# powerboard.net
KiCad netlist of a schematic drawn in EAGLE
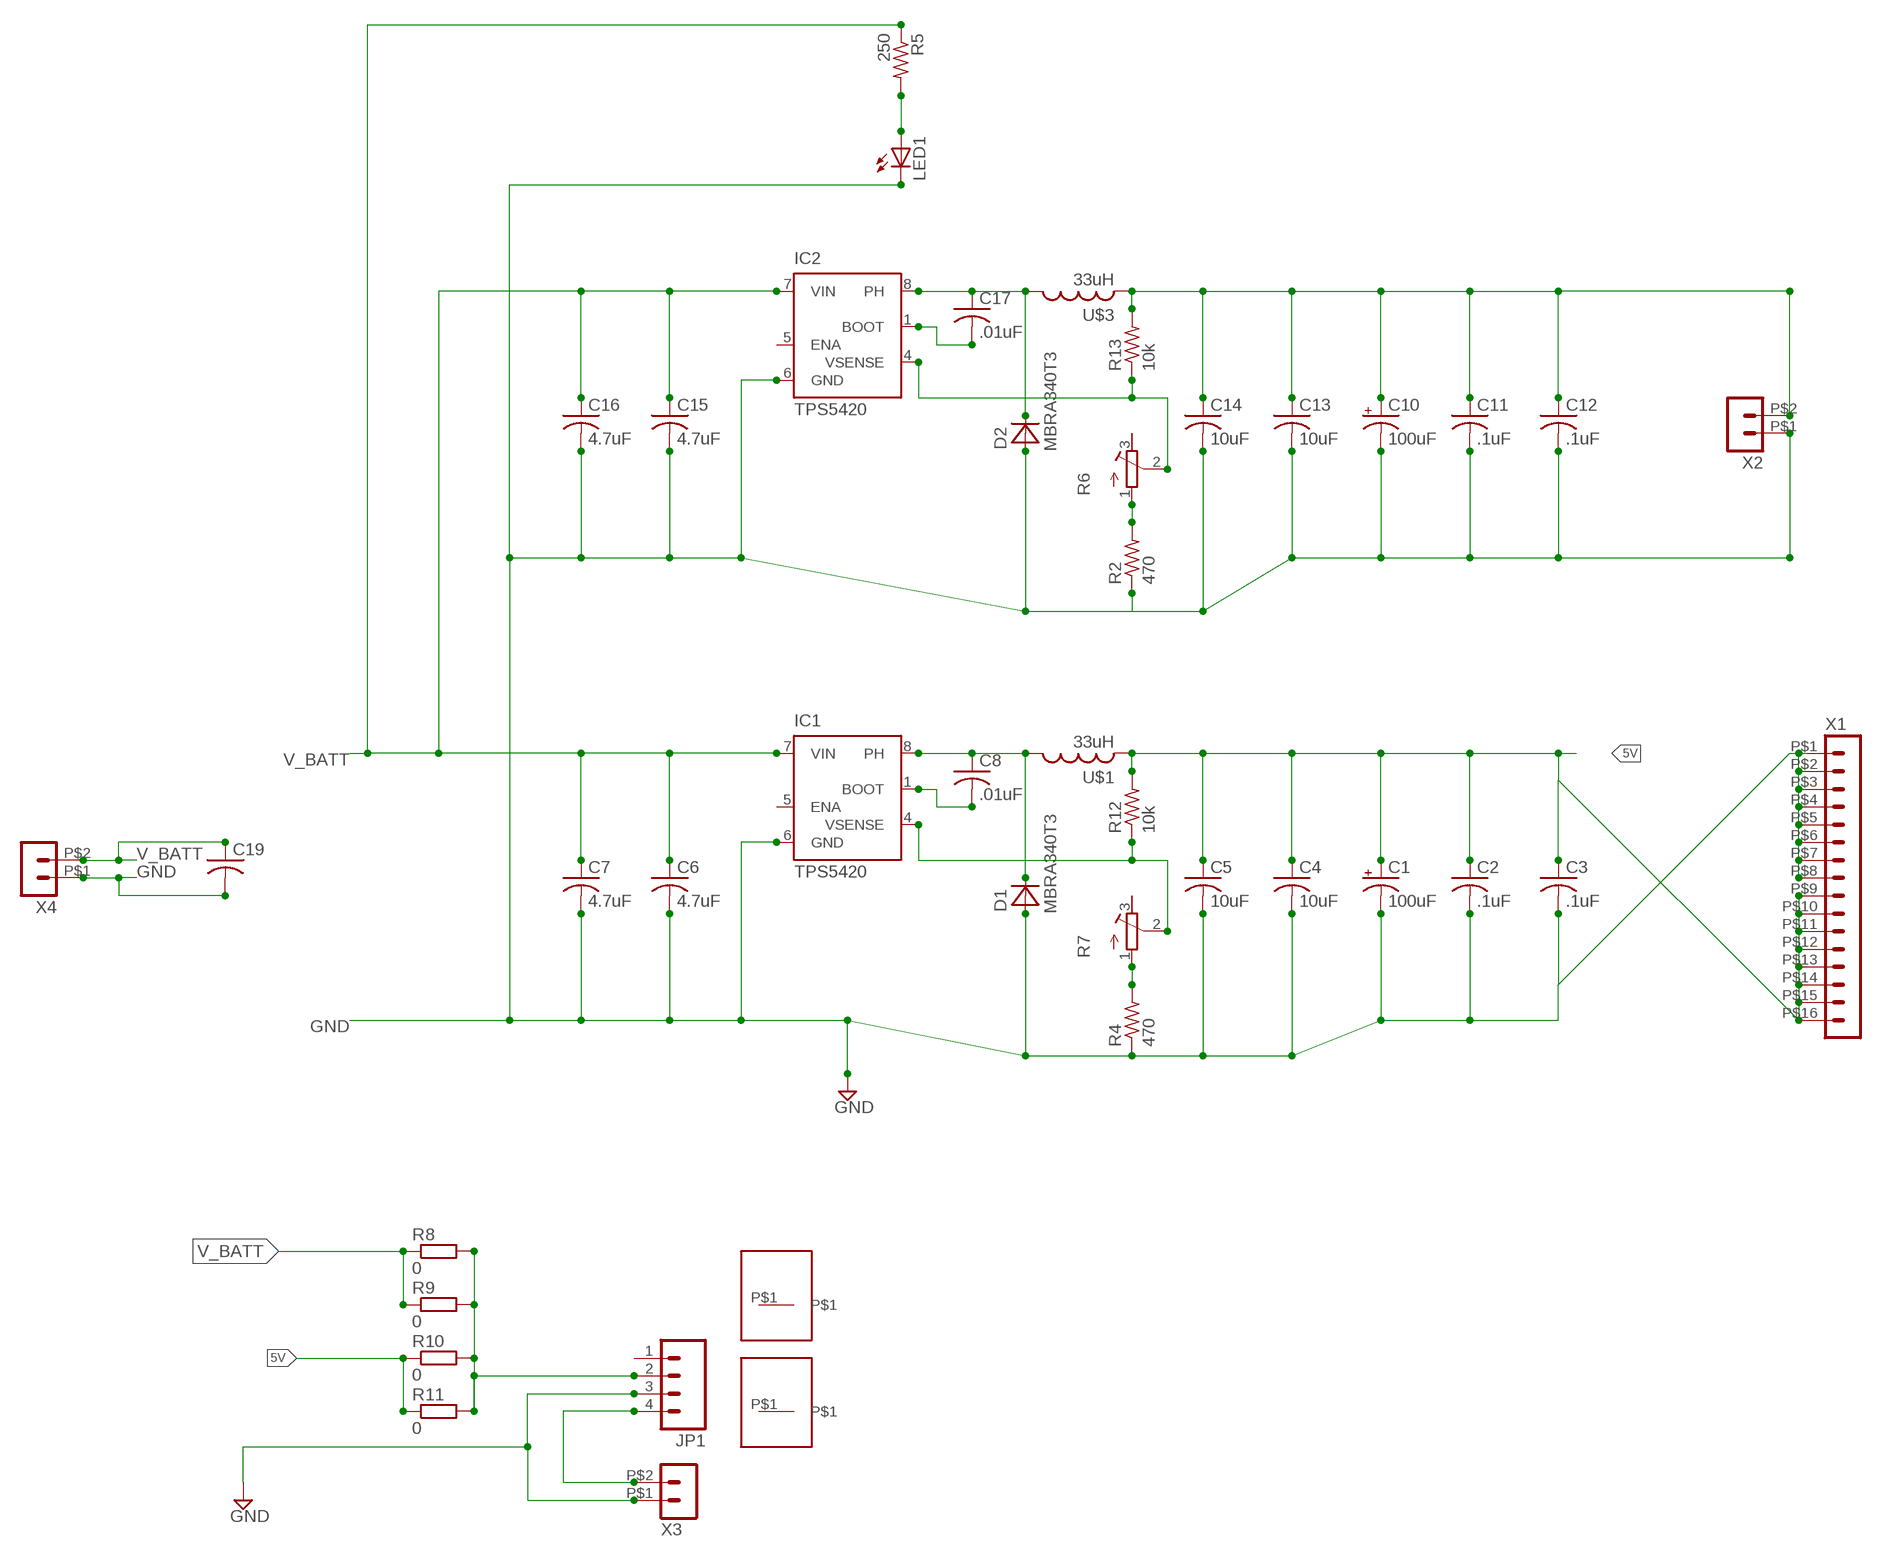
[diagram p0: schematic, sheet 1]

(export (version "E")
  (design (tool "Eeschema 10.0.6"))
  (components
    (comp (ref "C1")
      (value "100uF")
      (footprint "eagle-import:C_6032-28R")
      (libsource (lib "eagle-import") (part "CPOL-USC/6032-28R"))
    )
    (comp (ref "C2")
      (value ".1uF")
      (footprint "eagle-import:C1206K")
      (libsource (lib "eagle-import") (part "rcl_C-USC1206K"))
    )
    (comp (ref "C3")
      (value ".1uF")
      (footprint "eagle-import:C1206K")
      (libsource (lib "eagle-import") (part "rcl_C-USC1206K"))
    )
    (comp (ref "C4")
      (value "10uF")
      (footprint "eagle-import:C1206K")
      (libsource (lib "eagle-import") (part "rcl_C-USC1206K"))
    )
    (comp (ref "C5")
      (value "10uF")
      (footprint "eagle-import:C1206K")
      (libsource (lib "eagle-import") (part "rcl_C-USC1206K"))
    )
    (comp (ref "C6")
      (value "4.7uF")
      (footprint "eagle-import:C1812K")
      (libsource (lib "eagle-import") (part "rcl_C-USC1812K"))
    )
    (comp (ref "C7")
      (value "4.7uF")
      (footprint "eagle-import:C1812K")
      (libsource (lib "eagle-import") (part "rcl_C-USC1812K"))
    )
    (comp (ref "C8")
      (value ".01uF")
      (footprint "eagle-import:C0805K")
      (libsource (lib "eagle-import") (part "rcl_C-USC0805K"))
    )
    (comp (ref "C10")
      (value "100uF")
      (footprint "eagle-import:C_6032-28R")
      (libsource (lib "eagle-import") (part "CPOL-USC/6032-28R"))
    )
    (comp (ref "C11")
      (value ".1uF")
      (footprint "eagle-import:C1206K")
      (libsource (lib "eagle-import") (part "rcl_C-USC1206K"))
    )
    (comp (ref "C12")
      (value ".1uF")
      (footprint "eagle-import:C1206K")
      (libsource (lib "eagle-import") (part "rcl_C-USC1206K"))
    )
    (comp (ref "C13")
      (value "10uF")
      (footprint "eagle-import:C1206K")
      (libsource (lib "eagle-import") (part "rcl_C-USC1206K"))
    )
    (comp (ref "C14")
      (value "10uF")
      (footprint "eagle-import:C1206K")
      (libsource (lib "eagle-import") (part "rcl_C-USC1206K"))
    )
    (comp (ref "C15")
      (value "4.7uF")
      (footprint "eagle-import:C1812K")
      (libsource (lib "eagle-import") (part "rcl_C-USC1812K"))
    )
    (comp (ref "C16")
      (value "4.7uF")
      (footprint "eagle-import:C1812K")
      (libsource (lib "eagle-import") (part "rcl_C-USC1812K"))
    )
    (comp (ref "C17")
      (value ".01uF")
      (footprint "eagle-import:C0805K")
      (libsource (lib "eagle-import") (part "rcl_C-USC0805K"))
    )
    (comp (ref "C19")
      (value "C-USC2220K")
      (footprint "eagle-import:C2220K")
      (libsource (lib "eagle-import") (part "C-USC2220K"))
    )
    (comp (ref "D1")
      (value "MBRA340T3")
      (footprint "eagle-import:SMA")
      (libsource (lib "eagle-import") (part "MBRA340T3"))
    )
    (comp (ref "D2")
      (value "MBRA340T3")
      (footprint "eagle-import:SMA")
      (libsource (lib "eagle-import") (part "MBRA340T3"))
    )
    (comp (ref "IC1")
      (value "TPS5420")
      (footprint "eagle-import:D_R-PDSO-G08")
      (fields (field (name "MPN") "TPS5410DR"))
      (libsource (lib "eagle-import") (part "TPS5420"))
    )
    (comp (ref "IC2")
      (value "TPS5420")
      (footprint "eagle-import:D_R-PDSO-G08")
      (fields (field (name "MPN") "TPS5410DR"))
      (libsource (lib "eagle-import") (part "TPS5420"))
    )
    (comp (ref "JP1")
      (value "M04LOCK")
      (footprint "eagle-import:1X04_LOCK")
      (libsource (lib "eagle-import") (part "M04LOCK"))
    )
    (comp (ref "LED1")
      (value "LEDSML1206")
      (footprint "eagle-import:SML1206")
      (libsource (lib "eagle-import") (part "LEDSML1206"))
    )
    (comp (ref "R2")
      (value "470")
      (footprint "eagle-import:R3216")
      (libsource (lib "eagle-import") (part "R-US_R3216"))
    )
    (comp (ref "R4")
      (value "470")
      (footprint "eagle-import:R3216")
      (libsource (lib "eagle-import") (part "R-US_R3216"))
    )
    (comp (ref "R5")
      (value "250")
      (footprint "eagle-import:R1206")
      (libsource (lib "eagle-import") (part "R-US_R1206"))
    )
    (comp (ref "R6")
      (value "R-TRIMM3224W")
      (footprint "eagle-import:RTRIM3224W")
      (libsource (lib "eagle-import") (part "R-TRIMM3224W"))
    )
    (comp (ref "R7")
      (value "R-TRIMM3224W")
      (footprint "eagle-import:RTRIM3224W")
      (libsource (lib "eagle-import") (part "R-TRIMM3224W"))
    )
    (comp (ref "R8")
      (value "0")
      (footprint "eagle-import:R0805")
      (libsource (lib "eagle-import") (part "R-EU_R0805"))
    )
    (comp (ref "R9")
      (value "0")
      (footprint "eagle-import:R0805")
      (libsource (lib "eagle-import") (part "R-EU_R0805"))
    )
    (comp (ref "R10")
      (value "0")
      (footprint "eagle-import:R0805")
      (libsource (lib "eagle-import") (part "R-EU_R0805"))
    )
    (comp (ref "R11")
      (value "0")
      (footprint "eagle-import:R0805")
      (libsource (lib "eagle-import") (part "R-EU_R0805"))
    )
    (comp (ref "R12")
      (value "10k")
      (footprint "eagle-import:M0805")
      (libsource (lib "eagle-import") (part "R-US_M0805"))
    )
    (comp (ref "R13")
      (value "10k")
      (footprint "eagle-import:M0805")
      (libsource (lib "eagle-import") (part "R-US_M0805"))
    )
    (comp (ref "U$1")
      (value "33uH")
      (footprint "eagle-import:MSS1260")
      (libsource (lib "eagle-import") (part "MSS1260"))
    )
    (comp (ref "U$2")
      (value "THERMAL_PAD")
      (footprint "eagle-import:THERMAL_PAD")
      (libsource (lib "eagle-import") (part "THERMAL_PAD"))
    )
    (comp (ref "U$3")
      (value "33uH")
      (footprint "eagle-import:MSS1260")
      (libsource (lib "eagle-import") (part "MSS1260"))
    )
    (comp (ref "U$4")
      (value "THERMAL_PAD")
      (footprint "eagle-import:THERMAL_PAD")
      (libsource (lib "eagle-import") (part "THERMAL_PAD"))
    )
    (comp (ref "X1")
      (value "HEADER_POS16_43045-1606")
      (footprint "eagle-import:43045-1606")
      (libsource (lib "eagle-import") (part "HEADER_POS16_?43045-1606"))
    )
    (comp (ref "X2")
      (value "HEADER_POS2_43045-0206")
      (footprint "eagle-import:43045-0206")
      (libsource (lib "eagle-import") (part "HEADER_POS2_?43045-0206"))
    )
    (comp (ref "X3")
      (value "HEADER_POS2_43045-0206")
      (footprint "eagle-import:43045-0206")
      (libsource (lib "eagle-import") (part "HEADER_POS2_?43045-0206"))
    )
    (comp (ref "X4")
      (value "HEADER_POS2_43045-0206")
      (footprint "eagle-import:43045-0206")
      (libsource (lib "eagle-import") (part "HEADER_POS2_?43045-0206"))
    )
  )
  (nets
    (net (code "1") (name "5V") (class "Default")
      (node (ref "C1") (pin "+") (pinfunction "+_+") (pintype "passive"))
      (node (ref "C2") (pin "1") (pinfunction "1_1") (pintype "passive"))
      (node (ref "C3") (pin "1") (pinfunction "1_1") (pintype "passive"))
      (node (ref "C4") (pin "1") (pinfunction "1_1") (pintype "passive"))
      (node (ref "C5") (pin "1") (pinfunction "1_1") (pintype "passive"))
      (node (ref "R10") (pin "1") (pinfunction "1_1") (pintype "passive"))
      (node (ref "R11") (pin "1") (pinfunction "1_1") (pintype "passive"))
      (node (ref "R12") (pin "2") (pinfunction "2_2") (pintype "passive"))
      (node (ref "U$1") (pin "P$2") (pinfunction "P$2_P$2") (pintype "passive"))
      (node (ref "U$1") (pin "P$4") (pinfunction "P$2_P$4") (pintype "passive"))
      (node (ref "X1") (pin "P$10") (pinfunction "10_P$10") (pintype "passive"))
      (node (ref "X1") (pin "P$11") (pinfunction "11_P$11") (pintype "passive"))
      (node (ref "X1") (pin "P$12") (pinfunction "12_P$12") (pintype "passive"))
      (node (ref "X1") (pin "P$13") (pinfunction "13_P$13") (pintype "passive"))
      (node (ref "X1") (pin "P$14") (pinfunction "14_P$14") (pintype "passive"))
      (node (ref "X1") (pin "P$15") (pinfunction "15_P$15") (pintype "passive"))
      (node (ref "X1") (pin "P$16") (pinfunction "16_P$16") (pintype "passive"))
      (node (ref "X1") (pin "P$9") (pinfunction "9_P$9") (pintype "passive"))
    )
    (net (code "2") (name "GND") (class "Default")
      (node (ref "C1") (pin "-") (pinfunction "-_-") (pintype "passive"))
      (node (ref "C10") (pin "-") (pinfunction "-_-") (pintype "passive"))
      (node (ref "C11") (pin "2") (pinfunction "2_2") (pintype "passive"))
      (node (ref "C12") (pin "2") (pinfunction "2_2") (pintype "passive"))
      (node (ref "C13") (pin "2") (pinfunction "2_2") (pintype "passive"))
      (node (ref "C14") (pin "2") (pinfunction "2_2") (pintype "passive"))
      (node (ref "C15") (pin "2") (pinfunction "2_2") (pintype "passive"))
      (node (ref "C16") (pin "2") (pinfunction "2_2") (pintype "passive"))
      (node (ref "C19") (pin "2") (pinfunction "2_2") (pintype "passive"))
      (node (ref "C2") (pin "2") (pinfunction "2_2") (pintype "passive"))
      (node (ref "C3") (pin "2") (pinfunction "2_2") (pintype "passive"))
      (node (ref "C4") (pin "2") (pinfunction "2_2") (pintype "passive"))
      (node (ref "C5") (pin "2") (pinfunction "2_2") (pintype "passive"))
      (node (ref "C6") (pin "2") (pinfunction "2_2") (pintype "passive"))
      (node (ref "C7") (pin "2") (pinfunction "2_2") (pintype "passive"))
      (node (ref "D1") (pin "A") (pinfunction "A_A") (pintype "passive"))
      (node (ref "D2") (pin "A") (pinfunction "A_A") (pintype "passive"))
      (node (ref "IC1") (pin "6") (pinfunction "GND_6") (pintype "power_in"))
      (node (ref "IC2") (pin "6") (pinfunction "GND_6") (pintype "power_in"))
      (node (ref "JP1") (pin "3") (pinfunction "3_3") (pintype "passive"))
      (node (ref "LED1") (pin "C") (pinfunction "C_C") (pintype "passive"))
      (node (ref "R2") (pin "1") (pinfunction "1_1") (pintype "passive"))
      (node (ref "R4") (pin "1") (pinfunction "1_1") (pintype "passive"))
      (node (ref "X1") (pin "P$1") (pinfunction "1_P$1") (pintype "passive"))
      (node (ref "X1") (pin "P$2") (pinfunction "2_P$2") (pintype "passive"))
      (node (ref "X1") (pin "P$3") (pinfunction "3_P$3") (pintype "passive"))
      (node (ref "X1") (pin "P$4") (pinfunction "4_P$4") (pintype "passive"))
      (node (ref "X1") (pin "P$5") (pinfunction "5_P$5") (pintype "passive"))
      (node (ref "X1") (pin "P$6") (pinfunction "6_P$6") (pintype "passive"))
      (node (ref "X1") (pin "P$7") (pinfunction "7_P$7") (pintype "passive"))
      (node (ref "X1") (pin "P$8") (pinfunction "8_P$8") (pintype "passive"))
      (node (ref "X2") (pin "P$1") (pinfunction "1_P$1") (pintype "passive"))
      (node (ref "X3") (pin "P$1") (pinfunction "1_P$1") (pintype "passive"))
      (node (ref "X4") (pin "P$1") (pinfunction "1_P$1") (pintype "passive"))
    )
    (net (code "3") (name "Net-(IC1-BOOT)") (class "Default")
      (node (ref "C8") (pin "2") (pinfunction "2_2") (pintype "passive"))
      (node (ref "IC1") (pin "1") (pinfunction "BOOT_1") (pintype "output"))
    )
    (net (code "4") (name "Net-(IC1-PH)") (class "Default")
      (node (ref "C8") (pin "1") (pinfunction "1_1") (pintype "passive"))
      (node (ref "D1") (pin "C") (pinfunction "C_C") (pintype "passive"))
      (node (ref "IC1") (pin "8") (pinfunction "PH_8") (pintype "output"))
      (node (ref "U$1") (pin "P$1") (pinfunction "P$1_P$1") (pintype "passive"))
      (node (ref "U$1") (pin "P$3") (pinfunction "P$1_P$3") (pintype "passive"))
    )
    (net (code "5") (name "Net-(IC1-VSENSE)") (class "Default")
      (node (ref "IC1") (pin "4") (pinfunction "VSENSE_4") (pintype "input"))
      (node (ref "R12") (pin "1") (pinfunction "1_1") (pintype "passive"))
      (node (ref "R7") (pin "2") (pinfunction "S_2") (pintype "passive"))
    )
    (net (code "6") (name "Net-(IC2-BOOT)") (class "Default")
      (node (ref "C17") (pin "2") (pinfunction "2_2") (pintype "passive"))
      (node (ref "IC2") (pin "1") (pinfunction "BOOT_1") (pintype "output"))
    )
    (net (code "7") (name "Net-(IC2-PH)") (class "Default")
      (node (ref "C17") (pin "1") (pinfunction "1_1") (pintype "passive"))
      (node (ref "D2") (pin "C") (pinfunction "C_C") (pintype "passive"))
      (node (ref "IC2") (pin "8") (pinfunction "PH_8") (pintype "output"))
      (node (ref "U$3") (pin "P$1") (pinfunction "P$1_P$1") (pintype "passive"))
      (node (ref "U$3") (pin "P$3") (pinfunction "P$1_P$3") (pintype "passive"))
    )
    (net (code "8") (name "Net-(IC2-VSENSE)") (class "Default")
      (node (ref "IC2") (pin "4") (pinfunction "VSENSE_4") (pintype "input"))
      (node (ref "R13") (pin "1") (pinfunction "1_1") (pintype "passive"))
      (node (ref "R6") (pin "2") (pinfunction "S_2") (pintype "passive"))
    )
    (net (code "9") (name "Net-(JP1-Pad2)") (class "Default")
      (node (ref "JP1") (pin "2") (pinfunction "2_2") (pintype "passive"))
      (node (ref "R10") (pin "2") (pinfunction "2_2") (pintype "passive"))
      (node (ref "R11") (pin "2") (pinfunction "2_2") (pintype "passive"))
      (node (ref "R8") (pin "2") (pinfunction "2_2") (pintype "passive"))
      (node (ref "R9") (pin "2") (pinfunction "2_2") (pintype "passive"))
    )
    (net (code "10") (name "Net-(LED1-PadA)") (class "Default")
      (node (ref "LED1") (pin "A") (pinfunction "A_A") (pintype "passive"))
      (node (ref "R5") (pin "2") (pinfunction "2_2") (pintype "passive"))
    )
    (net (code "11") (name "Net-(R6-A)") (class "Default")
      (node (ref "R2") (pin "2") (pinfunction "2_2") (pintype "passive"))
      (node (ref "R6") (pin "1") (pinfunction "A_1") (pintype "passive"))
    )
    (net (code "12") (name "Net-(R7-A)") (class "Default")
      (node (ref "R4") (pin "2") (pinfunction "2_2") (pintype "passive"))
      (node (ref "R7") (pin "1") (pinfunction "A_1") (pintype "passive"))
    )
    (net (code "13") (name "Net-(X2-2)") (class "Default")
      (node (ref "C10") (pin "+") (pinfunction "+_+") (pintype "passive"))
      (node (ref "C11") (pin "1") (pinfunction "1_1") (pintype "passive"))
      (node (ref "C12") (pin "1") (pinfunction "1_1") (pintype "passive"))
      (node (ref "C13") (pin "1") (pinfunction "1_1") (pintype "passive"))
      (node (ref "C14") (pin "1") (pinfunction "1_1") (pintype "passive"))
      (node (ref "R13") (pin "2") (pinfunction "2_2") (pintype "passive"))
      (node (ref "U$3") (pin "P$2") (pinfunction "P$2_P$2") (pintype "passive"))
      (node (ref "U$3") (pin "P$4") (pinfunction "P$2_P$4") (pintype "passive"))
      (node (ref "X2") (pin "P$2") (pinfunction "2_P$2") (pintype "passive"))
    )
    (net (code "14") (name "Net-(X3-2)") (class "Default")
      (node (ref "JP1") (pin "4") (pinfunction "4_4") (pintype "passive"))
      (node (ref "X3") (pin "P$2") (pinfunction "2_P$2") (pintype "passive"))
    )
    (net (code "15") (name "V_BATT") (class "Default")
      (node (ref "C15") (pin "1") (pinfunction "1_1") (pintype "passive"))
      (node (ref "C16") (pin "1") (pinfunction "1_1") (pintype "passive"))
      (node (ref "C19") (pin "1") (pinfunction "1_1") (pintype "passive"))
      (node (ref "C6") (pin "1") (pinfunction "1_1") (pintype "passive"))
      (node (ref "C7") (pin "1") (pinfunction "1_1") (pintype "passive"))
      (node (ref "IC1") (pin "7") (pinfunction "VIN_7") (pintype "input"))
      (node (ref "IC2") (pin "7") (pinfunction "VIN_7") (pintype "input"))
      (node (ref "R5") (pin "1") (pinfunction "1_1") (pintype "passive"))
      (node (ref "R8") (pin "1") (pinfunction "1_1") (pintype "passive"))
      (node (ref "R9") (pin "1") (pinfunction "1_1") (pintype "passive"))
      (node (ref "X4") (pin "P$2") (pinfunction "2_P$2") (pintype "passive"))
    )
    (net (code "16") (name "unconnected-(IC1-ENA-Pad5)") (class "Default")
      (node (ref "IC1") (pin "5") (pinfunction "ENA_5") (pintype "input"))
    )
    (net (code "17") (name "unconnected-(IC2-ENA-Pad5)") (class "Default")
      (node (ref "IC2") (pin "5") (pinfunction "ENA_5") (pintype "input"))
    )
    (net (code "18") (name "unconnected-(JP1-Pad1)") (class "Default")
      (node (ref "JP1") (pin "1") (pinfunction "1_1") (pintype "passive"))
    )
    (net (code "19") (name "unconnected-(R6-E-Pad3)") (class "Default")
      (node (ref "R6") (pin "3") (pinfunction "E_3") (pintype "passive"))
    )
    (net (code "20") (name "unconnected-(R7-E-Pad3)") (class "Default")
      (node (ref "R7") (pin "3") (pinfunction "E_3") (pintype "passive"))
    )
    (net (code "21") (name "unconnected-(U$2-PadP$1)") (class "Default")
      (node (ref "U$2") (pin "P$1") (pinfunction "P$1_P$1") (pintype "bidirectional"))
    )
    (net (code "22") (name "unconnected-(U$4-PadP$1)") (class "Default")
      (node (ref "U$4") (pin "P$1") (pinfunction "P$1_P$1") (pintype "bidirectional"))
    )
  )
)
